# FPGA1.net
KiCad netlist of a schematic drawn in Altium Designer
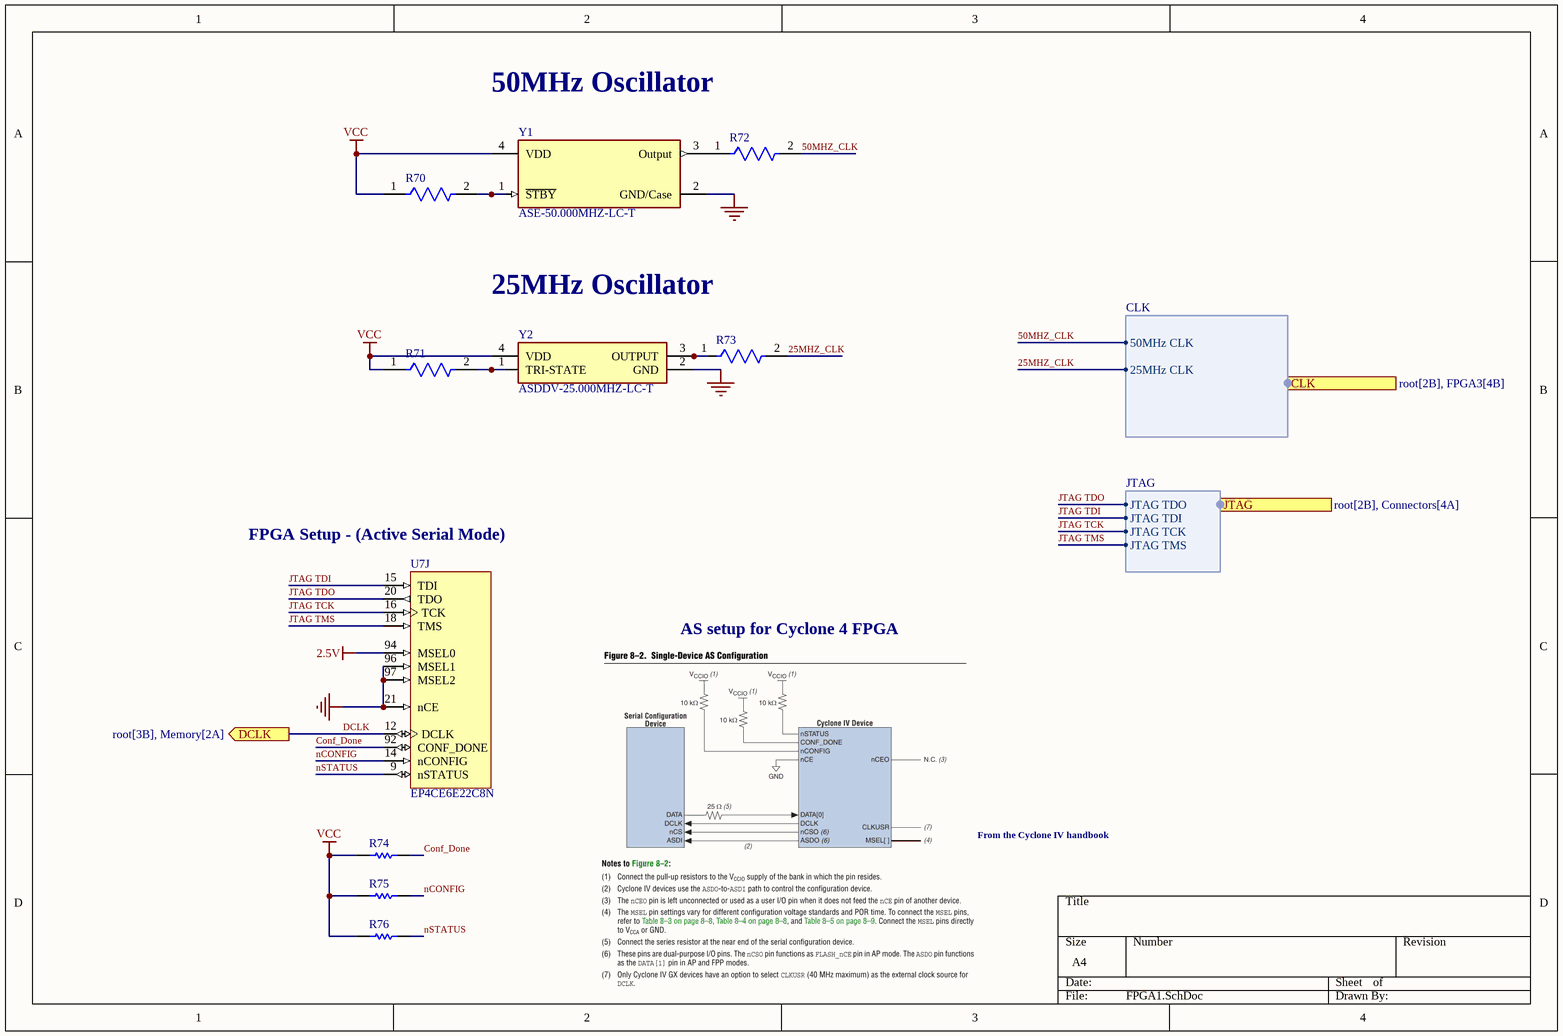
[diagram p0: FPGA1.SchDoc]

(export (version "E")
  (design (tool "Eeschema 10.0.6"))
  (components
    (comp (ref "R70")
      (value "RC0603FR-073K3L")
      (footprint "FP-RC0603-0_55-MFG")
      (fields (field (name "TOLERANCE") "1%"))
      (libsource (lib "Altium Content Vault") (part "1029c3af85768c4190bb7ad29bc67b5"))
    )
    (comp (ref "R71")
      (value "RC0603FR-073K3L")
      (footprint "FP-RC0603-0_55-MFG")
      (fields (field (name "TOLERANCE") "1%"))
      (libsource (lib "Altium Content Vault") (part "1029c3af85768c4190bb7ad29bc67b5"))
    )
    (comp (ref "R72")
      (value "RT0402BRE0733RL")
      (footprint "FP-RT0402-MFG")
      (description "RES SMD 33 OHM 0.1% 1/16W 0402")
      (fields (field (name "TOLERANCE") "0.001") (field (name "MANUFACTURER") "Yageo"))
      (libsource (lib "Altium Content Vault") (part "1029c3af85768c4190bb7ad29bc67b5"))
    )
    (comp (ref "R73")
      (value "RT0402BRE0733RL")
      (footprint "FP-RT0402-MFG")
      (description "RES SMD 33 OHM 0.1% 1/16W 0402")
      (fields (field (name "TOLERANCE") "0.001") (field (name "MANUFACTURER") "Yageo"))
      (libsource (lib "Altium Content Vault") (part "1029c3af85768c4190bb7ad29bc67b5"))
    )
    (comp (ref "R74")
      (value "RC0402FR-0710KL")
      (footprint "RESC1005X40X25LL05T10")
      (fields (field (name "MANUFACTURER") "Yageo / Phycomp"))
      (libsource (lib "Altium Content Vault") (part "RES"))
    )
    (comp (ref "R75")
      (value "RC0402FR-0710KL")
      (footprint "RESC1005X40X25LL05T10")
      (fields (field (name "MANUFACTURER") "Yageo / Phycomp"))
      (libsource (lib "Altium Content Vault") (part "RES"))
    )
    (comp (ref "R76")
      (value "RC0402FR-0710KL")
      (footprint "RESC1005X40X25LL05T10")
      (fields (field (name "MANUFACTURER") "Yageo / Phycomp"))
      (libsource (lib "Altium Content Vault") (part "RES"))
    )
    (comp (ref "U7")
      (value "EP4CE6E22C8N")
      (footprint "EQFP144_A-165_D2-54_M")
      (fields (field (name "MANUFACTURER") "Altera"))
      (libsource (lib "Altium Content Vault") (part "FPGA-ALEP4C-EP4CE6-E144"))
    )
    (comp (ref "Y1")
      (value "ASE-50.000MHZ-LC-T")
      (footprint "FP-ASE-MFG")
      (description "XTAL Oscillator 50MHz ±50ppm CMOS 3.3V 4-SMD 3.2mm x 2.5mm")
      (libsource (lib "Altium Content Vault") (part "61a724e6190563596ac712fef61ad37"))
    )
    (comp (ref "Y2")
      (value "ASDDV-25.000MHZ-LC-T")
      (footprint "SOP80P1176X120-54N:AbraconASDDV")
      (description "Crystal or Oscillator")
      (fields (field (name "MOUSER PART NUMBER") "815-ASDDV-2500MHZLCT"))
      (libsource (lib "*") (part "ASDDV-25.000MHZ-LC-T"))
    )
  )
  (nets
    (net (code "3") (name "/25MHZ_CLK") (class "Default")
      (node (ref "R73") (pin "2") (pinfunction "2_2") (pintype "passive"))
    )
    (net (code "4") (name "/50MHZ_CLK") (class "Default")
      (node (ref "R72") (pin "2") (pinfunction "2_2") (pintype "passive"))
    )
    (net (code "5") (name "/Conf_Done") (class "Default")
      (node (ref "R74") (pin "2") (pinfunction "2_2") (pintype "passive"))
      (node (ref "U7") (pin "92") (pinfunction "CONF_DONE_92") (pintype "bidirectional"))
    )
    (net (code "6") (name "/DCLK") (class "Default")
      (node (ref "U7") (pin "12") (pinfunction "DCLK_12") (pintype "bidirectional"))
    )
    (net (code "7") (name "/JTAG TCK") (class "Default")
      (node (ref "U7") (pin "16") (pinfunction "TCK_16") (pintype "input"))
    )
    (net (code "8") (name "/JTAG TDI") (class "Default")
      (node (ref "U7") (pin "15") (pinfunction "TDI_15") (pintype "input"))
    )
    (net (code "9") (name "/JTAG TDO") (class "Default")
      (node (ref "U7") (pin "20") (pinfunction "TDO_20") (pintype "output"))
    )
    (net (code "10") (name "/JTAG TMS") (class "Default")
      (node (ref "U7") (pin "18") (pinfunction "TMS_18") (pintype "input"))
    )
    (net (code "11") (name "/nCONFIG") (class "Default")
      (node (ref "R75") (pin "2") (pinfunction "2_2") (pintype "passive"))
      (node (ref "U7") (pin "14") (pinfunction "nCONFIG_14") (pintype "input"))
    )
    (net (code "12") (name "/nSTATUS") (class "Default")
      (node (ref "R76") (pin "2") (pinfunction "2_2") (pintype "passive"))
      (node (ref "U7") (pin "9") (pinfunction "nSTATUS_9") (pintype "bidirectional"))
    )
    (net (code "15") (name "2.5V") (class "Default")
      (node (ref "U7") (pin "94") (pinfunction "MSEL0_94") (pintype "input"))
    )
    (net (code "16") (name "GND") (class "Default")
      (node (ref "U7") (pin "21") (pinfunction "nCE_21") (pintype "input"))
      (node (ref "U7") (pin "96") (pinfunction "MSEL1_96") (pintype "input"))
      (node (ref "U7") (pin "97") (pinfunction "MSEL2_97") (pintype "input"))
      (node (ref "Y1") (pin "2") (pinfunction "GND/Case_2") (pintype "power_in"))
      (node (ref "Y2") (pin "2") (pinfunction "GND_2") (pintype "passive"))
    )
    (net (code "17") (name "Net-(Y1-Output)") (class "Default")
      (node (ref "R72") (pin "1") (pinfunction "1_1") (pintype "passive"))
      (node (ref "Y1") (pin "3") (pinfunction "Output_3") (pintype "output"))
    )
    (net (code "18") (name "Net-(Y1-~{STBY})") (class "Default")
      (node (ref "R70") (pin "2") (pinfunction "2_2") (pintype "passive"))
      (node (ref "Y1") (pin "1") (pinfunction "~{STBY}_1") (pintype "input"))
    )
    (net (code "19") (name "Net-(Y2-OUTPUT)") (class "Default")
      (node (ref "R73") (pin "1") (pinfunction "1_1") (pintype "passive"))
      (node (ref "Y2") (pin "3") (pinfunction "OUTPUT_3") (pintype "passive"))
    )
    (net (code "20") (name "Net-(Y2-TRI-STATE)") (class "Default")
      (node (ref "R71") (pin "2") (pinfunction "2_2") (pintype "passive"))
      (node (ref "Y2") (pin "1") (pinfunction "TRI-STATE_1") (pintype "passive"))
    )
    (net (code "21") (name "VCC") (class "Default")
      (node (ref "R70") (pin "1") (pinfunction "1_1") (pintype "passive"))
      (node (ref "R71") (pin "1") (pinfunction "1_1") (pintype "passive"))
      (node (ref "R74") (pin "1") (pinfunction "1_1") (pintype "passive"))
      (node (ref "R75") (pin "1") (pinfunction "1_1") (pintype "passive"))
      (node (ref "R76") (pin "1") (pinfunction "1_1") (pintype "passive"))
      (node (ref "Y1") (pin "4") (pinfunction "VDD_4") (pintype "power_in"))
      (node (ref "Y2") (pin "4") (pinfunction "VDD_4") (pintype "passive"))
    )
  )
)
